# controller.net
KiCad netlist of a schematic drawn in EAGLE
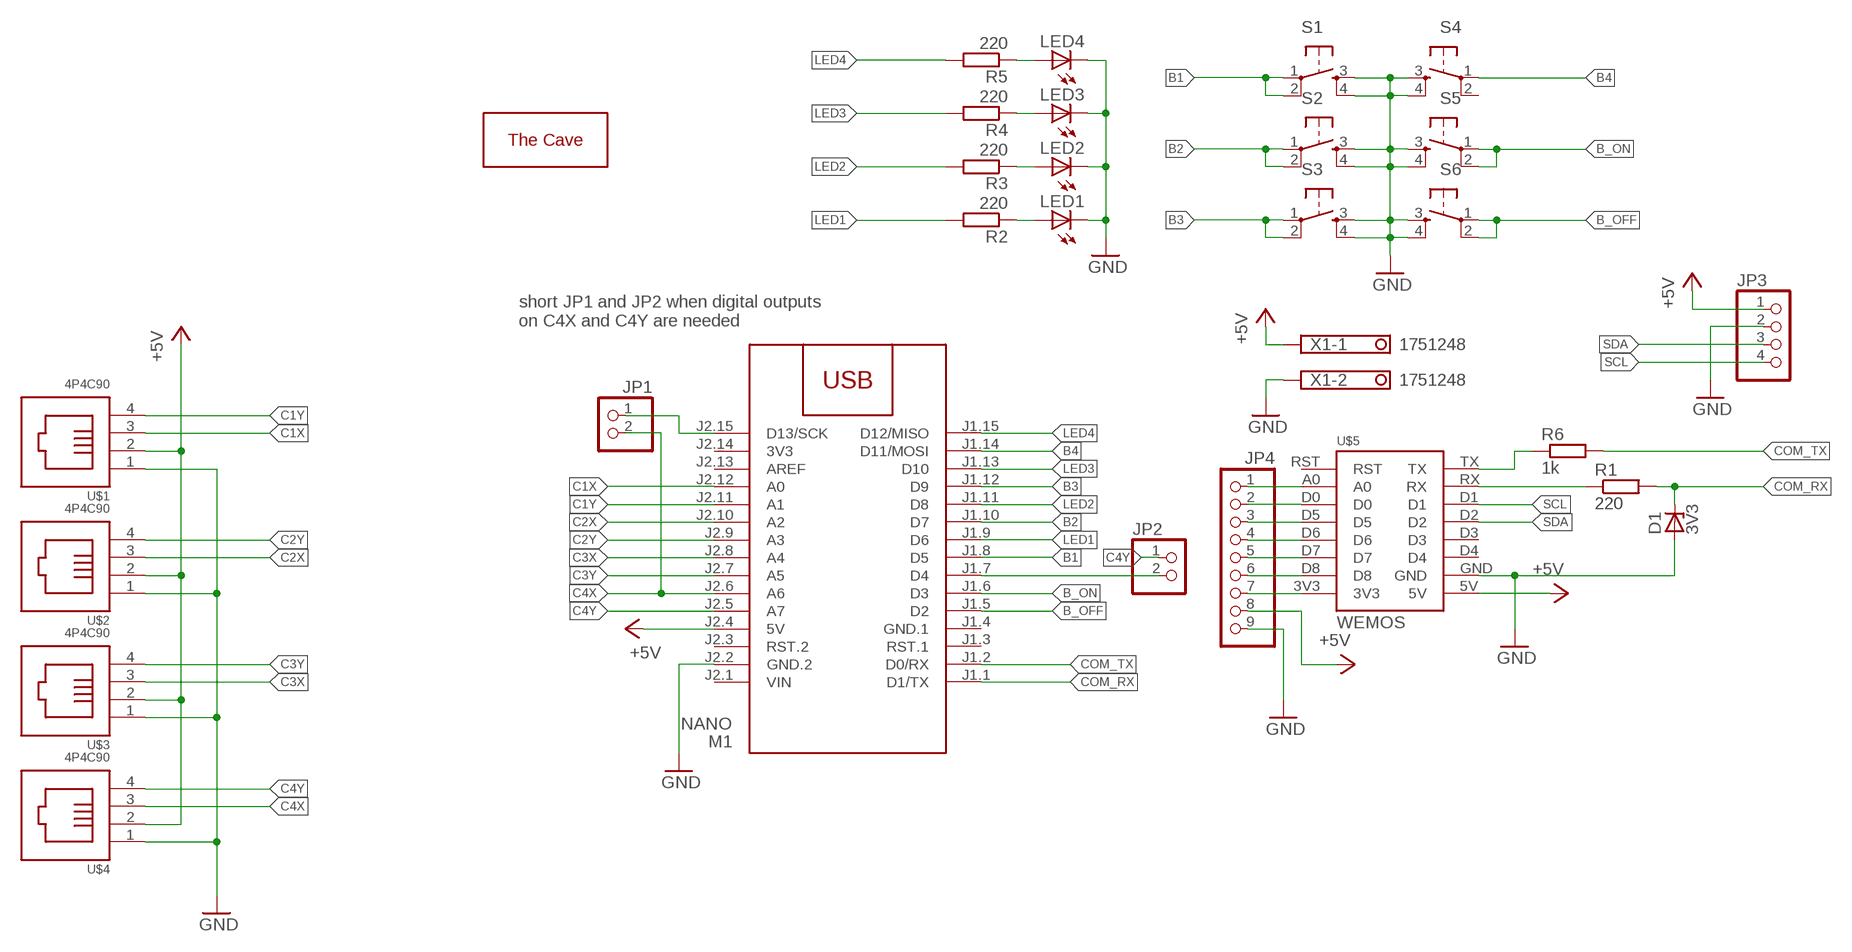
[diagram p0: schematic, sheet 1]

(export (version "E")
  (design (tool "Eeschema 10.0.6"))
  (components
    (comp (ref "D1")
      (value "3V3")
      (footprint "eagle-import:ZDIO-7.5")
      (libsource (lib "eagle-import") (part "ZENER-DIODEZD-7.5"))
    )
    (comp (ref "JP1")
      (value "PINHD-1X2")
      (footprint "eagle-import:1X02")
      (libsource (lib "eagle-import") (part "PINHD-1X2"))
    )
    (comp (ref "JP2")
      (value "PINHD-1X2")
      (footprint "eagle-import:1X02")
      (libsource (lib "eagle-import") (part "PINHD-1X2"))
    )
    (comp (ref "JP3")
      (value "PINHD-1X4")
      (footprint "eagle-import:1X04")
      (libsource (lib "eagle-import") (part "PINHD-1X4"))
    )
    (comp (ref "JP4")
      (value "PINHD-1X9")
      (footprint "eagle-import:1X09")
      (libsource (lib "eagle-import") (part "PINHD-1X9"))
    )
    (comp (ref "LED1")
      (value "LED5MM")
      (footprint "eagle-import:LED5MM")
      (libsource (lib "eagle-import") (part "LED5MM"))
    )
    (comp (ref "LED2")
      (value "LED5MM")
      (footprint "eagle-import:LED5MM")
      (libsource (lib "eagle-import") (part "LED5MM"))
    )
    (comp (ref "LED3")
      (value "LED5MM")
      (footprint "eagle-import:LED5MM")
      (libsource (lib "eagle-import") (part "LED5MM"))
    )
    (comp (ref "LED4")
      (value "LED5MM")
      (footprint "eagle-import:LED5MM")
      (libsource (lib "eagle-import") (part "LED5MM"))
    )
    (comp (ref "M1")
      (value "NANO")
      (footprint "eagle-import:ARDUINO-NANO-3.0#NOHOLE")
      (libsource (lib "eagle-import") (part "ARDUINO-NANO-3.0#NOHOLE"))
    )
    (comp (ref "R1")
      (value "220")
      (footprint "eagle-import:0207_10")
      (libsource (lib "eagle-import") (part "R-EU_0207/10"))
    )
    (comp (ref "R2")
      (value "220")
      (footprint "eagle-import:R0805")
      (libsource (lib "eagle-import") (part "R-EU_R0805"))
    )
    (comp (ref "R3")
      (value "220")
      (footprint "eagle-import:R0805")
      (libsource (lib "eagle-import") (part "R-EU_R0805"))
    )
    (comp (ref "R4")
      (value "220")
      (footprint "eagle-import:R0805")
      (libsource (lib "eagle-import") (part "R-EU_R0805"))
    )
    (comp (ref "R5")
      (value "220")
      (footprint "eagle-import:R0805")
      (libsource (lib "eagle-import") (part "R-EU_R0805"))
    )
    (comp (ref "R6")
      (value "1k")
      (footprint "eagle-import:0207_10")
      (libsource (lib "eagle-import") (part "R-EU_0207/10"))
    )
    (comp (ref "S1")
      (value "TACT-SWITCH-6MM-THT")
      (footprint "eagle-import:TACT-SWITCH-6MM-THT")
      (libsource (lib "eagle-import") (part "TACT-SWITCH-6MM-THT"))
    )
    (comp (ref "S2")
      (value "TACT-SWITCH-6MM-THT")
      (footprint "eagle-import:TACT-SWITCH-6MM-THT")
      (libsource (lib "eagle-import") (part "TACT-SWITCH-6MM-THT"))
    )
    (comp (ref "S3")
      (value "TACT-SWITCH-6MM-THT")
      (footprint "eagle-import:TACT-SWITCH-6MM-THT")
      (libsource (lib "eagle-import") (part "TACT-SWITCH-6MM-THT"))
    )
    (comp (ref "S4")
      (value "TACT-SWITCH-6MM-THT")
      (footprint "eagle-import:TACT-SWITCH-6MM-THT")
      (libsource (lib "eagle-import") (part "TACT-SWITCH-6MM-THT"))
    )
    (comp (ref "S5")
      (value "TACT-SWITCH-6MM-THT")
      (footprint "eagle-import:TACT-SWITCH-6MM-THT")
      (libsource (lib "eagle-import") (part "TACT-SWITCH-6MM-THT"))
    )
    (comp (ref "S6")
      (value "TACT-SWITCH-6MM-THT")
      (footprint "eagle-import:TACT-SWITCH-6MM-THT")
      (libsource (lib "eagle-import") (part "TACT-SWITCH-6MM-THT"))
    )
    (comp (ref "U$1")
      (value "4P4C90")
      (footprint "eagle-import:4P4C-90")
      (libsource (lib "eagle-import") (part "4P4C90"))
    )
    (comp (ref "U$2")
      (value "4P4C90")
      (footprint "eagle-import:4P4C-90")
      (libsource (lib "eagle-import") (part "4P4C90"))
    )
    (comp (ref "U$3")
      (value "4P4C90")
      (footprint "eagle-import:4P4C-90")
      (libsource (lib "eagle-import") (part "4P4C90"))
    )
    (comp (ref "U$4")
      (value "4P4C90")
      (footprint "eagle-import:4P4C-90")
      (libsource (lib "eagle-import") (part "4P4C90"))
    )
    (comp (ref "U$5")
      (value "WEMOS")
      (footprint "eagle-import:WEMOS")
      (libsource (lib "eagle-import") (part "WEMOS"))
    )
    (comp (ref "U$6")
      (value "THECAVE_LOGO_NEW_TOP_SMALL")
      (footprint "eagle-import:NEW_LOGO_SMALL_TOP")
      (libsource (lib "eagle-import") (part "THECAVE_LOGO_NEW_TOP_SMALL"))
    )
    (comp (ref "X1")
      (value "1751248")
      (footprint "eagle-import:1751248")
      (libsource (lib "eagle-import") (part "1751248"))
    )
  )
  (nets
    (net (code "1") (name "+5V") (class "Default")
      (node (ref "JP3") (pin "1") (pinfunction "1_1") (pintype "passive"))
      (node (ref "JP4") (pin "8") (pinfunction "8_8") (pintype "passive"))
      (node (ref "M1") (pin "J2.4") (pinfunction "5V_J2.4") (pintype "power_in"))
      (node (ref "U$1") (pin "2") (pinfunction "P$2_2") (pintype "bidirectional"))
      (node (ref "U$2") (pin "2") (pinfunction "P$2_2") (pintype "bidirectional"))
      (node (ref "U$3") (pin "2") (pinfunction "P$2_2") (pintype "bidirectional"))
      (node (ref "U$4") (pin "2") (pinfunction "P$2_2") (pintype "bidirectional"))
      (node (ref "U$5") (pin "5V") (pinfunction "5V_5V") (pintype "bidirectional"))
      (node (ref "X1") (pin "1") (pinfunction "K_1") (pintype "passive"))
    )
    (net (code "2") (name "/3V3") (class "Default")
      (node (ref "M1") (pin "J2.14") (pinfunction "3V3_J2.14") (pintype "power_in"))
    )
    (net (code "3") (name "/GND.1") (class "Default")
      (node (ref "M1") (pin "J1.4") (pinfunction "GND.1_J1.4") (pintype "power_in"))
    )
    (net (code "4") (name "/VIN") (class "Default")
      (node (ref "M1") (pin "J2.1") (pinfunction "VIN_J2.1") (pintype "power_in"))
    )
    (net (code "5") (name "B1") (class "Default")
      (node (ref "M1") (pin "J1.8") (pinfunction "D5_J1.8") (pintype "bidirectional"))
      (node (ref "S1") (pin "1") (pinfunction "1_1") (pintype "passive"))
      (node (ref "S1") (pin "2") (pinfunction "2_2") (pintype "passive"))
    )
    (net (code "6") (name "B2") (class "Default")
      (node (ref "M1") (pin "J1.10") (pinfunction "D7_J1.10") (pintype "bidirectional"))
      (node (ref "S2") (pin "1") (pinfunction "1_1") (pintype "passive"))
      (node (ref "S2") (pin "2") (pinfunction "2_2") (pintype "passive"))
    )
    (net (code "7") (name "B3") (class "Default")
      (node (ref "M1") (pin "J1.12") (pinfunction "D9_J1.12") (pintype "bidirectional"))
      (node (ref "S3") (pin "1") (pinfunction "1_1") (pintype "passive"))
      (node (ref "S3") (pin "2") (pinfunction "2_2") (pintype "passive"))
    )
    (net (code "8") (name "B4") (class "Default")
      (node (ref "M1") (pin "J1.14") (pinfunction "D11/MOSI_J1.14") (pintype "bidirectional"))
      (node (ref "S4") (pin "1") (pinfunction "1_1") (pintype "passive"))
    )
    (net (code "9") (name "B_OFF") (class "Default")
      (node (ref "M1") (pin "J1.5") (pinfunction "D2_J1.5") (pintype "bidirectional"))
      (node (ref "S6") (pin "1") (pinfunction "1_1") (pintype "passive"))
      (node (ref "S6") (pin "2") (pinfunction "2_2") (pintype "passive"))
    )
    (net (code "10") (name "B_ON") (class "Default")
      (node (ref "M1") (pin "J1.6") (pinfunction "D3_J1.6") (pintype "bidirectional"))
      (node (ref "S5") (pin "1") (pinfunction "1_1") (pintype "passive"))
      (node (ref "S5") (pin "2") (pinfunction "2_2") (pintype "passive"))
    )
    (net (code "11") (name "C1X") (class "Default")
      (node (ref "M1") (pin "J2.12") (pinfunction "A0_J2.12") (pintype "bidirectional"))
      (node (ref "U$1") (pin "3") (pinfunction "P$3_3") (pintype "bidirectional"))
    )
    (net (code "12") (name "C1Y") (class "Default")
      (node (ref "M1") (pin "J2.11") (pinfunction "A1_J2.11") (pintype "bidirectional"))
      (node (ref "U$1") (pin "4") (pinfunction "P$4_4") (pintype "bidirectional"))
    )
    (net (code "13") (name "C2X") (class "Default")
      (node (ref "M1") (pin "J2.10") (pinfunction "A2_J2.10") (pintype "bidirectional"))
      (node (ref "U$2") (pin "3") (pinfunction "P$3_3") (pintype "bidirectional"))
    )
    (net (code "14") (name "C2Y") (class "Default")
      (node (ref "M1") (pin "J2.9") (pinfunction "A3_J2.9") (pintype "bidirectional"))
      (node (ref "U$2") (pin "4") (pinfunction "P$4_4") (pintype "bidirectional"))
    )
    (net (code "15") (name "C3X") (class "Default")
      (node (ref "M1") (pin "J2.8") (pinfunction "A4_J2.8") (pintype "bidirectional"))
      (node (ref "U$3") (pin "3") (pinfunction "P$3_3") (pintype "bidirectional"))
    )
    (net (code "16") (name "C3Y") (class "Default")
      (node (ref "M1") (pin "J2.7") (pinfunction "A5_J2.7") (pintype "bidirectional"))
      (node (ref "U$3") (pin "4") (pinfunction "P$4_4") (pintype "bidirectional"))
    )
    (net (code "17") (name "C4X") (class "Default")
      (node (ref "JP1") (pin "2") (pinfunction "2_2") (pintype "passive"))
      (node (ref "M1") (pin "J2.6") (pinfunction "A6_J2.6") (pintype "bidirectional"))
      (node (ref "U$4") (pin "3") (pinfunction "P$3_3") (pintype "bidirectional"))
    )
    (net (code "18") (name "C4Y") (class "Default")
      (node (ref "JP2") (pin "1") (pinfunction "1_1") (pintype "passive"))
      (node (ref "M1") (pin "J2.5") (pinfunction "A7_J2.5") (pintype "bidirectional"))
      (node (ref "U$4") (pin "4") (pinfunction "P$4_4") (pintype "bidirectional"))
    )
    (net (code "19") (name "COM_RX") (class "Default")
      (node (ref "D1") (pin "C") (pinfunction "C_C") (pintype "passive"))
      (node (ref "M1") (pin "J1.1") (pinfunction "D1/TX_J1.1") (pintype "bidirectional"))
      (node (ref "R1") (pin "2") (pinfunction "2_2") (pintype "passive"))
    )
    (net (code "20") (name "COM_TX") (class "Default")
      (node (ref "M1") (pin "J1.2") (pinfunction "D0/RX_J1.2") (pintype "bidirectional"))
      (node (ref "R6") (pin "2") (pinfunction "2_2") (pintype "passive"))
    )
    (net (code "21") (name "GND") (class "Default")
      (node (ref "D1") (pin "A") (pinfunction "A_A") (pintype "passive"))
      (node (ref "JP3") (pin "2") (pinfunction "2_2") (pintype "passive"))
      (node (ref "JP4") (pin "9") (pinfunction "9_9") (pintype "passive"))
      (node (ref "LED1") (pin "K") (pinfunction "C_K") (pintype "passive"))
      (node (ref "LED2") (pin "K") (pinfunction "C_K") (pintype "passive"))
      (node (ref "LED3") (pin "K") (pinfunction "C_K") (pintype "passive"))
      (node (ref "LED4") (pin "K") (pinfunction "C_K") (pintype "passive"))
      (node (ref "M1") (pin "J2.2") (pinfunction "GND.2_J2.2") (pintype "power_in"))
      (node (ref "S1") (pin "3") (pinfunction "3_3") (pintype "passive"))
      (node (ref "S1") (pin "4") (pinfunction "4_4") (pintype "passive"))
      (node (ref "S2") (pin "3") (pinfunction "3_3") (pintype "passive"))
      (node (ref "S2") (pin "4") (pinfunction "4_4") (pintype "passive"))
      (node (ref "S3") (pin "3") (pinfunction "3_3") (pintype "passive"))
      (node (ref "S3") (pin "4") (pinfunction "4_4") (pintype "passive"))
      (node (ref "S4") (pin "3") (pinfunction "3_3") (pintype "passive"))
      (node (ref "S4") (pin "4") (pinfunction "4_4") (pintype "passive"))
      (node (ref "S5") (pin "3") (pinfunction "3_3") (pintype "passive"))
      (node (ref "S5") (pin "4") (pinfunction "4_4") (pintype "passive"))
      (node (ref "S6") (pin "3") (pinfunction "3_3") (pintype "passive"))
      (node (ref "S6") (pin "4") (pinfunction "4_4") (pintype "passive"))
      (node (ref "U$1") (pin "1") (pinfunction "P$1_1") (pintype "bidirectional"))
      (node (ref "U$2") (pin "1") (pinfunction "P$1_1") (pintype "bidirectional"))
      (node (ref "U$3") (pin "1") (pinfunction "P$1_1") (pintype "bidirectional"))
      (node (ref "U$4") (pin "1") (pinfunction "P$1_1") (pintype "bidirectional"))
      (node (ref "U$5") (pin "GND") (pinfunction "GND_GND") (pintype "bidirectional"))
      (node (ref "X1") (pin "2") (pinfunction "K_2") (pintype "passive"))
    )
    (net (code "22") (name "LED1") (class "Default")
      (node (ref "M1") (pin "J1.9") (pinfunction "D6_J1.9") (pintype "bidirectional"))
      (node (ref "R2") (pin "2") (pinfunction "2_2") (pintype "passive"))
    )
    (net (code "23") (name "LED2") (class "Default")
      (node (ref "M1") (pin "J1.11") (pinfunction "D8_J1.11") (pintype "bidirectional"))
      (node (ref "R3") (pin "2") (pinfunction "2_2") (pintype "passive"))
    )
    (net (code "24") (name "LED3") (class "Default")
      (node (ref "M1") (pin "J1.13") (pinfunction "D10_J1.13") (pintype "bidirectional"))
      (node (ref "R4") (pin "2") (pinfunction "2_2") (pintype "passive"))
    )
    (net (code "25") (name "LED4") (class "Default")
      (node (ref "M1") (pin "J1.15") (pinfunction "D12/MISO_J1.15") (pintype "bidirectional"))
      (node (ref "R5") (pin "2") (pinfunction "2_2") (pintype "passive"))
    )
    (net (code "26") (name "Net-(JP4-Pad1)") (class "Default")
      (node (ref "JP4") (pin "1") (pinfunction "1_1") (pintype "passive"))
      (node (ref "U$5") (pin "A0") (pinfunction "A0_A0") (pintype "bidirectional"))
    )
    (net (code "27") (name "Net-(JP4-Pad2)") (class "Default")
      (node (ref "JP4") (pin "2") (pinfunction "2_2") (pintype "passive"))
      (node (ref "U$5") (pin "D0") (pinfunction "D0_D0") (pintype "bidirectional"))
    )
    (net (code "28") (name "Net-(JP4-Pad3)") (class "Default")
      (node (ref "JP4") (pin "3") (pinfunction "3_3") (pintype "passive"))
      (node (ref "U$5") (pin "D5") (pinfunction "D5_D5") (pintype "bidirectional"))
    )
    (net (code "29") (name "Net-(JP4-Pad4)") (class "Default")
      (node (ref "JP4") (pin "4") (pinfunction "4_4") (pintype "passive"))
      (node (ref "U$5") (pin "D6") (pinfunction "D6_D6") (pintype "bidirectional"))
    )
    (net (code "30") (name "Net-(JP4-Pad5)") (class "Default")
      (node (ref "JP4") (pin "5") (pinfunction "5_5") (pintype "passive"))
      (node (ref "U$5") (pin "D7") (pinfunction "D7_D7") (pintype "bidirectional"))
    )
    (net (code "31") (name "Net-(JP4-Pad6)") (class "Default")
      (node (ref "JP4") (pin "6") (pinfunction "6_6") (pintype "passive"))
      (node (ref "U$5") (pin "D8") (pinfunction "D8_D8") (pintype "bidirectional"))
    )
    (net (code "32") (name "Net-(JP4-Pad7)") (class "Default")
      (node (ref "JP4") (pin "7") (pinfunction "7_7") (pintype "passive"))
      (node (ref "U$5") (pin "3V3") (pinfunction "3V3_3V3") (pintype "bidirectional"))
    )
    (net (code "33") (name "Net-(LED1-PadA)") (class "Default")
      (node (ref "LED1") (pin "A") (pinfunction "A_A") (pintype "passive"))
      (node (ref "R2") (pin "1") (pinfunction "1_1") (pintype "passive"))
    )
    (net (code "34") (name "Net-(LED2-PadA)") (class "Default")
      (node (ref "LED2") (pin "A") (pinfunction "A_A") (pintype "passive"))
      (node (ref "R3") (pin "1") (pinfunction "1_1") (pintype "passive"))
    )
    (net (code "35") (name "Net-(LED3-PadA)") (class "Default")
      (node (ref "LED3") (pin "A") (pinfunction "A_A") (pintype "passive"))
      (node (ref "R4") (pin "1") (pinfunction "1_1") (pintype "passive"))
    )
    (net (code "36") (name "Net-(LED4-PadA)") (class "Default")
      (node (ref "LED4") (pin "A") (pinfunction "A_A") (pintype "passive"))
      (node (ref "R5") (pin "1") (pinfunction "1_1") (pintype "passive"))
    )
    (net (code "37") (name "Net-(M1-D4)") (class "Default")
      (node (ref "JP2") (pin "2") (pinfunction "2_2") (pintype "passive"))
      (node (ref "M1") (pin "J1.7") (pinfunction "D4_J1.7") (pintype "bidirectional"))
    )
    (net (code "38") (name "Net-(M1-D13{slash}SCK)") (class "Default")
      (node (ref "JP1") (pin "1") (pinfunction "1_1") (pintype "passive"))
      (node (ref "M1") (pin "J2.15") (pinfunction "D13/SCK_J2.15") (pintype "bidirectional"))
    )
    (net (code "39") (name "Net-(R1-Pad1)") (class "Default")
      (node (ref "R1") (pin "1") (pinfunction "1_1") (pintype "passive"))
      (node (ref "U$5") (pin "RX") (pinfunction "RX_RX") (pintype "bidirectional"))
    )
    (net (code "40") (name "Net-(R6-Pad1)") (class "Default")
      (node (ref "R6") (pin "1") (pinfunction "1_1") (pintype "passive"))
      (node (ref "U$5") (pin "TX") (pinfunction "TX_TX") (pintype "bidirectional"))
    )
    (net (code "41") (name "SCL") (class "Default")
      (node (ref "JP3") (pin "4") (pinfunction "4_4") (pintype "passive"))
      (node (ref "U$5") (pin "D1") (pinfunction "D1_D1") (pintype "bidirectional"))
    )
    (net (code "42") (name "SDA") (class "Default")
      (node (ref "JP3") (pin "3") (pinfunction "3_3") (pintype "passive"))
      (node (ref "U$5") (pin "D2") (pinfunction "D2_D2") (pintype "bidirectional"))
    )
    (net (code "43") (name "unconnected-(M1-AREF-PadJ2.13)") (class "Default")
      (node (ref "M1") (pin "J2.13") (pinfunction "AREF_J2.13") (pintype "bidirectional"))
    )
    (net (code "44") (name "unconnected-(M1-RST.1-PadJ1.3)") (class "Default")
      (node (ref "M1") (pin "J1.3") (pinfunction "RST.1_J1.3") (pintype "bidirectional"))
    )
    (net (code "45") (name "unconnected-(M1-RST.2-PadJ2.3)") (class "Default")
      (node (ref "M1") (pin "J2.3") (pinfunction "RST.2_J2.3") (pintype "bidirectional"))
    )
    (net (code "46") (name "unconnected-(S4-Pad2)") (class "Default")
      (node (ref "S4") (pin "2") (pinfunction "2_2") (pintype "passive"))
    )
    (net (code "47") (name "unconnected-(U$5-PadD3)") (class "Default")
      (node (ref "U$5") (pin "D3") (pinfunction "D3_D3") (pintype "bidirectional"))
    )
    (net (code "48") (name "unconnected-(U$5-PadD4)") (class "Default")
      (node (ref "U$5") (pin "D4") (pinfunction "D4_D4") (pintype "bidirectional"))
    )
    (net (code "49") (name "unconnected-(U$5-PadRST)") (class "Default")
      (node (ref "U$5") (pin "RST") (pinfunction "RST_RST") (pintype "bidirectional"))
    )
  )
)
